# Quad_FC_V10_6.net
KiCad netlist of a schematic drawn in Altium Designer
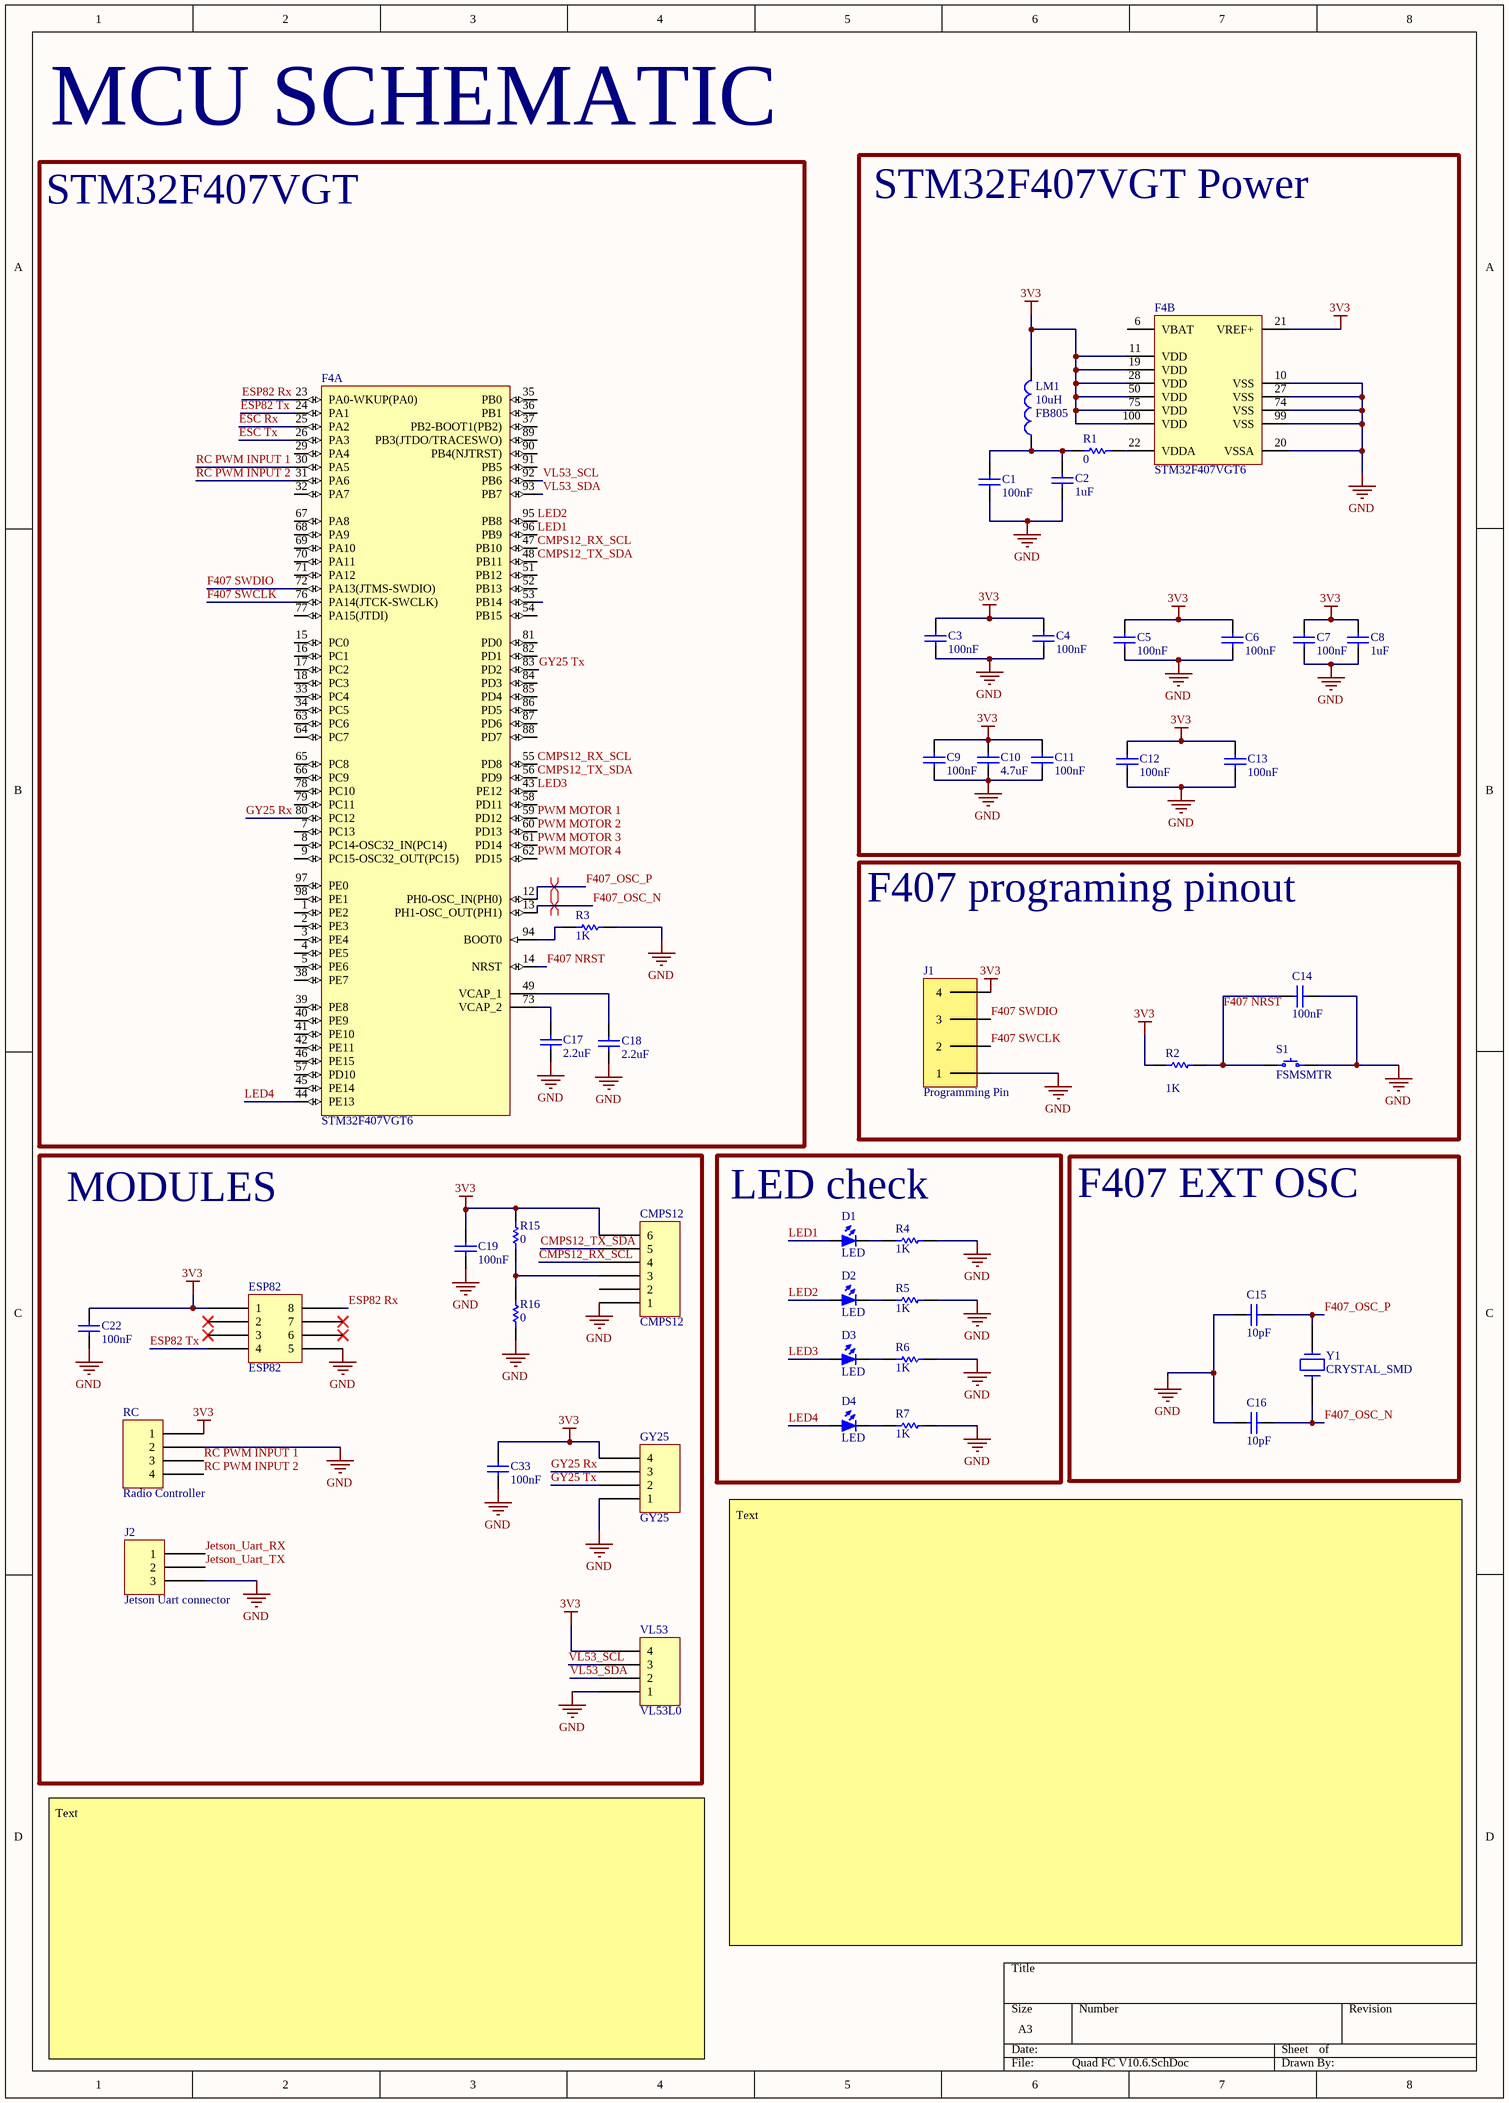
[diagram p0: Quad FC V10.6.SchDoc]

(export (version "E")
  (design (tool "Eeschema 10.0.6"))
  (components
    (comp (ref "C1")
      (value "100nF")
      (footprint "CAP0603")
      (description "F407VET6 Power CAP")
      (fields (field (name "DESIGNER") "Abbas Basereh"))
      (libsource (lib "2017AbbasBasereh9365731239 -ver1") (part "CAP SMD PACKAGE"))
    )
    (comp (ref "C2")
      (value "1uF")
      (footprint "CAP0603")
      (description "F407VET6 Power CAP")
      (fields (field (name "DESIGNER") "Abbas Basereh"))
      (libsource (lib "2017AbbasBasereh9365731239 -ver1") (part "CAP SMD PACKAGE"))
    )
    (comp (ref "C3")
      (value "100nF")
      (footprint "CAP0603")
      (description "F407VET6 Power CAP")
      (fields (field (name "DESIGNER") "Abbas Basereh"))
      (libsource (lib "2017AbbasBasereh9365731239 -ver1") (part "CAP SMD PACKAGE"))
    )
    (comp (ref "C4")
      (value "100nF")
      (footprint "CAP0603")
      (description "F407VET6 Power CAP")
      (fields (field (name "DESIGNER") "Abbas Basereh"))
      (libsource (lib "2017AbbasBasereh9365731239 -ver1") (part "CAP SMD PACKAGE"))
    )
    (comp (ref "C5")
      (value "100nF")
      (footprint "CAP0603")
      (description "F407VET6 Power CAP")
      (fields (field (name "DESIGNER") "Abbas Basereh"))
      (libsource (lib "2017AbbasBasereh9365731239 -ver1") (part "CAP SMD PACKAGE"))
    )
    (comp (ref "C6")
      (value "100nF")
      (footprint "CAP0603")
      (description "F407VET6 Power CAP")
      (fields (field (name "DESIGNER") "Abbas Basereh"))
      (libsource (lib "2017AbbasBasereh9365731239 -ver1") (part "CAP SMD PACKAGE"))
    )
    (comp (ref "C7")
      (value "100nF")
      (footprint "CAP0603")
      (description "F407VET6 Power CAP")
      (fields (field (name "DESIGNER") "Abbas Basereh"))
      (libsource (lib "2017AbbasBasereh9365731239 -ver1") (part "CAP SMD PACKAGE"))
    )
    (comp (ref "C8")
      (value "1uF")
      (footprint "CAP0603")
      (description "F407VET6 Power CAP")
      (fields (field (name "DESIGNER") "Abbas Basereh"))
      (libsource (lib "2017AbbasBasereh9365731239 -ver1") (part "CAP SMD PACKAGE"))
    )
    (comp (ref "C9")
      (value "100nF")
      (footprint "CAP0603")
      (description "F407VET6 Power CAP")
      (fields (field (name "DESIGNER") "Abbas Basereh"))
      (libsource (lib "2017AbbasBasereh9365731239 -ver1") (part "CAP SMD PACKAGE"))
    )
    (comp (ref "C10")
      (value "4.7uF")
      (footprint "CAP0603")
      (description "F407VET6 Power CAP")
      (fields (field (name "DESIGNER") "Abbas Basereh"))
      (libsource (lib "2017AbbasBasereh9365731239 -ver1") (part "CAP SMD PACKAGE"))
    )
    (comp (ref "C11")
      (value "100nF")
      (footprint "CAP0603")
      (description "F407VET6 Power CAP")
      (fields (field (name "DESIGNER") "Abbas Basereh"))
      (libsource (lib "2017AbbasBasereh9365731239 -ver1") (part "CAP SMD PACKAGE"))
    )
    (comp (ref "C12")
      (value "100nF")
      (footprint "CAP0603")
      (description "F407VET6 Power CAP")
      (fields (field (name "DESIGNER") "Abbas Basereh"))
      (libsource (lib "2017AbbasBasereh9365731239 -ver1") (part "CAP SMD PACKAGE"))
    )
    (comp (ref "C13")
      (value "100nF")
      (footprint "CAP0603")
      (description "F407VET6 Power CAP")
      (fields (field (name "DESIGNER") "Abbas Basereh"))
      (libsource (lib "2017AbbasBasereh9365731239 -ver1") (part "CAP SMD PACKAGE"))
    )
    (comp (ref "C14")
      (value "100nF")
      (footprint "CAP0603")
      (description "F407VET6 Power CAP")
      (fields (field (name "DESIGNER") "Abbas Basereh"))
      (libsource (lib "2017AbbasBasereh9365731239 -ver1") (part "CAP SMD PACKAGE"))
    )
    (comp (ref "C15")
      (value "10pF")
      (footprint "CAP0603")
      (description "F407VET6 Power CAP")
      (fields (field (name "DESIGNER") "Abbas Basereh"))
      (libsource (lib "2017AbbasBasereh9365731239 -ver1") (part "CAP SMD PACKAGE"))
    )
    (comp (ref "C16")
      (value "10pF")
      (footprint "CAP0603")
      (description "F407VET6 Power CAP")
      (fields (field (name "DESIGNER") "Abbas Basereh"))
      (libsource (lib "2017AbbasBasereh9365731239 -ver1") (part "CAP SMD PACKAGE"))
    )
    (comp (ref "C17")
      (value "2.2uF")
      (footprint "CAP0603")
      (description "F407VET6 Power CAP")
      (fields (field (name "DESIGNER") "Abbas Basereh"))
      (libsource (lib "2017AbbasBasereh9365731239 -ver1") (part "CAP SMD PACKAGE"))
    )
    (comp (ref "C18")
      (value "2.2uF")
      (footprint "CAP0603")
      (description "F407VET6 Power CAP")
      (fields (field (name "DESIGNER") "Abbas Basereh"))
      (libsource (lib "2017AbbasBasereh9365731239 -ver1") (part "CAP SMD PACKAGE"))
    )
    (comp (ref "C19")
      (value "100nF")
      (footprint "CAP0603")
      (description "F407VET6 Power CAP")
      (fields (field (name "DESIGNER") "Abbas Basereh"))
      (libsource (lib "2017AbbasBasereh9365731239 -ver1") (part "CAP SMD PACKAGE"))
    )
    (comp (ref "C22")
      (value "100nF")
      (footprint "CAP0603")
      (description "F407VET6 Power CAP")
      (fields (field (name "DESIGNER") "Abbas Basereh"))
      (libsource (lib "2017AbbasBasereh9365731239 -ver1") (part "CAP SMD PACKAGE"))
    )
    (comp (ref "C33")
      (value "100nF")
      (footprint "CAP0603")
      (description "F407VET6 Power CAP")
      (fields (field (name "DESIGNER") "Abbas Basereh"))
      (libsource (lib "2017AbbasBasereh9365731239 -ver1") (part "CAP SMD PACKAGE"))
    )
    (comp (ref "CMPS12")
      (value "CMPS12")
      (footprint "SAMTEC SSW-106-03-T-S")
      (description "CONN RCPT 6POS 0.1 TIN PCB")
      (fields (field (name "PART NUMBER") "SSW-106-03-T-S") (field (name "MANUFACTURER") "Samtec Inc."))
      (libsource (lib "Celestial Altium Library - altium_library (1)") (part "6 Pin"))
    )
    (comp (ref "D1")
      (value "LED")
      (footprint "0603 - LED")
      (description "Led")
      (fields (field (name "PUBLISHER") "Altium Limited"))
      (libsource (lib "Sajad_Altium_Library") (part "LED"))
    )
    (comp (ref "D2")
      (value "LED")
      (footprint "0603 - LED")
      (description "Led")
      (fields (field (name "PUBLISHER") "Altium Limited"))
      (libsource (lib "Sajad_Altium_Library") (part "LED"))
    )
    (comp (ref "D3")
      (value "LED")
      (footprint "0603 - LED")
      (description "Led")
      (fields (field (name "PUBLISHER") "Altium Limited"))
      (libsource (lib "Sajad_Altium_Library") (part "LED"))
    )
    (comp (ref "D4")
      (value "LED")
      (footprint "0603 - LED")
      (description "Led")
      (fields (field (name "PUBLISHER") "Altium Limited"))
      (libsource (lib "Sajad_Altium_Library") (part "LED"))
    )
    (comp (ref "ESP82")
      (value "ESP82")
      (footprint "HARWIN M20-7830445")
      (description "CONN RCPT 8POS 0.1 GOLD PCB")
      (fields (field (name "PART NUMBER") "M20-7830442") (field (name "MANUFACTURER") "Harwin Inc."))
      (libsource (lib "Celestial Altium Library - altium_library (1)") (part "2X4 PIN DU"))
    )
    (comp (ref "F4")
      (value "STM32F407VGT6")
      (footprint "STM-LQFP100_N")
      (fields (field (name "MANUFACTURER") "STMicroelectronics"))
      (libsource (lib "STMicroelectronics STM32 F4") (part "STM32F407VGT6"))
    )
    (comp (ref "GY25")
      (value "GY25")
      (footprint "SAMTEC SSW-104-03-T-S")
      (description "CONN RCPT 4POS 0.1 TIN PCB")
      (fields (field (name "PART NUMBER") "SSW-104-03-T-S") (field (name "MANUFACTURER") "Samtec Inc."))
      (libsource (lib "Celestial Altium Library - altium_library (1)") (part "4 Pin"))
    )
    (comp (ref "J1")
      (value "Programming Pin")
      (footprint "HEADER 4X1")
      (libsource (lib "AltiumLib1") (part "Header4X1"))
    )
    (comp (ref "J2")
      (value "Jetson Uart connector")
      (footprint "JST XH B3B-XH-A")
      (description "CONN HEADER VERT 3POS 2.5MM")
      (fields
        (field (name "PART NUMBER") "B3B-XH-A(LF)(SN)")
        (field (name "MANUFACTURER") "JST Sales America Inc.")
      )
      (libsource (lib "Celestial Altium Library - altium_library (1)") (part "3 Pin"))
    )
    (comp (ref "LM1")
      (value "10uH")
      (footprint "0805L")
      (description "Inductor")
      (fields (field (name "ALTIUM_VALUE") "FB805") (field (name "PUBLISHER") "Altium Limited"))
      (libsource (lib "2017AbbasBasereh9365731239 -ver1") (part "L SMA 0.25W"))
    )
    (comp (ref "R1")
      (value "0")
      (footprint "RES0603")
      (description "TOTAL SMD RESISTOR PACK")
      (fields (field (name "DESIGNER") "Abbas Basereh"))
      (libsource (lib "2017AbbasBasereh9365731239 -ver1") (part "RES SMD PACKAGE"))
    )
    (comp (ref "R2")
      (value "1K")
      (footprint "RES0603")
      (description "TOTAL SMD RESISTOR PACK")
      (fields (field (name "DESIGNER") "Abbas Basereh"))
      (libsource (lib "2017AbbasBasereh9365731239 -ver1") (part "RES SMD PACKAGE"))
    )
    (comp (ref "R3")
      (value "1K")
      (footprint "RES0603")
      (description "TOTAL SMD RESISTOR PACK")
      (fields (field (name "DESIGNER") "Abbas Basereh"))
      (libsource (lib "2017AbbasBasereh9365731239 -ver1") (part "RES SMD PACKAGE"))
    )
    (comp (ref "R4")
      (value "1K")
      (footprint "RES0603")
      (description "TOTAL SMD RESISTOR PACK")
      (fields (field (name "DESIGNER") "Abbas Basereh"))
      (libsource (lib "2017AbbasBasereh9365731239 -ver1") (part "RES SMD PACKAGE"))
    )
    (comp (ref "R5")
      (value "1K")
      (footprint "RES0603")
      (description "TOTAL SMD RESISTOR PACK")
      (fields (field (name "DESIGNER") "Abbas Basereh"))
      (libsource (lib "2017AbbasBasereh9365731239 -ver1") (part "RES SMD PACKAGE"))
    )
    (comp (ref "R6")
      (value "1K")
      (footprint "RES0603")
      (description "TOTAL SMD RESISTOR PACK")
      (fields (field (name "DESIGNER") "Abbas Basereh"))
      (libsource (lib "2017AbbasBasereh9365731239 -ver1") (part "RES SMD PACKAGE"))
    )
    (comp (ref "R7")
      (value "1K")
      (footprint "RES0603")
      (description "TOTAL SMD RESISTOR PACK")
      (fields (field (name "DESIGNER") "Abbas Basereh"))
      (libsource (lib "2017AbbasBasereh9365731239 -ver1") (part "RES SMD PACKAGE"))
    )
    (comp (ref "R15")
      (value "0")
      (footprint "RES0603")
      (description "TOTAL SMD RESISTOR PACK")
      (fields (field (name "DESIGNER") "Abbas Basereh"))
      (libsource (lib "2017AbbasBasereh9365731239 -ver1") (part "RES SMD PACKAGE"))
    )
    (comp (ref "R16")
      (value "0")
      (footprint "RES0603")
      (description "TOTAL SMD RESISTOR PACK")
      (fields (field (name "DESIGNER") "Abbas Basereh"))
      (libsource (lib "2017AbbasBasereh9365731239 -ver1") (part "RES SMD PACKAGE"))
    )
    (comp (ref "RC")
      (value "Radio Controller")
      (footprint "JST SM04B-GHS-TB")
      (description "CONN HEADER SMD R/A 4POS 1.25MM")
      (fields
        (field (name "PART NUMBER") "SM04B-GHS-TB(LF)(SN)-")
        (field (name "MANUFACTURER") "JST Sales America Inc.")
      )
      (libsource (lib "") (part "4 Pin_1"))
    )
    (comp (ref "S1")
      (value "FSMSMTR")
      (footprint "TE FSMSMTR")
      (description "SWITCH TACTILE SPST-NO 0.05A 24V")
      (fields (field (name "MANUFACTURER") "TE Connectivity ALCOSWITCH Switches"))
      (libsource (lib "Celestial Altium Library - altium_library (1)") (part "SPST-NO 2 PIN"))
    )
    (comp (ref "VL53")
      (value "VL53L0")
      (footprint "JST SM04B-GHS-TB")
      (description "CONN HEADER SMD R/A 4POS 1.25MM")
      (fields
        (field (name "PART NUMBER") "SM04B-GHS-TB(LF)(SN)-")
        (field (name "MANUFACTURER") "JST Sales America Inc.")
      )
      (libsource (lib "Celestial Altium Library - altium_library (1)") (part "4 Pin"))
    )
    (comp (ref "Y1")
      (value "CRYSTAL_SMD")
      (footprint "My_Crystal - SMD")
      (description "Crystal")
      (libsource (lib "AMINLIB") (part "CRYSTAL_SMD"))
    )
  )
  (nets
    (net (code "1") (name "/CMPS12_RX_SCL") (class "Default")
      (node (ref "CMPS12") (pin "4") (pinfunction "4_4") (pintype "passive"))
      (node (ref "F4") (pin "47") (pinfunction "PB10_47") (pintype "bidirectional"))
      (node (ref "F4") (pin "55") (pinfunction "PD8_55") (pintype "bidirectional"))
    )
    (net (code "2") (name "/CMPS12_TX_SDA") (class "Default")
      (node (ref "CMPS12") (pin "5") (pinfunction "5_5") (pintype "passive"))
      (node (ref "F4") (pin "48") (pinfunction "PB11_48") (pintype "bidirectional"))
      (node (ref "F4") (pin "56") (pinfunction "PD9_56") (pintype "bidirectional"))
    )
    (net (code "3") (name "/ESC Rx") (class "Default")
      (node (ref "F4") (pin "25") (pinfunction "PA2_25") (pintype "bidirectional"))
    )
    (net (code "4") (name "/ESC Tx") (class "Default")
      (node (ref "F4") (pin "26") (pinfunction "PA3_26") (pintype "bidirectional"))
    )
    (net (code "5") (name "/ESP82 Rx") (class "Default")
      (node (ref "ESP82") (pin "8") (pinfunction "8_8") (pintype "passive"))
      (node (ref "F4") (pin "23") (pinfunction "PA0-WKUP(PA0)_23") (pintype "bidirectional"))
    )
    (net (code "6") (name "/ESP82 Tx") (class "Default")
      (node (ref "ESP82") (pin "4") (pinfunction "4_4") (pintype "passive"))
      (node (ref "F4") (pin "24") (pinfunction "PA1_24") (pintype "bidirectional"))
    )
    (net (code "7") (name "/F407 NRST") (class "Default")
      (node (ref "C14") (pin "1") (pinfunction "1_1") (pintype "passive"))
      (node (ref "F4") (pin "14") (pinfunction "NRST_14") (pintype "bidirectional"))
      (node (ref "R2") (pin "2") (pinfunction "2_2") (pintype "passive"))
      (node (ref "S1") (pin "1") (pinfunction "1_1") (pintype "passive"))
    )
    (net (code "8") (name "/F407 SWCLK") (class "Default")
      (node (ref "F4") (pin "76") (pinfunction "PA14(JTCK-SWCLK)_76") (pintype "bidirectional"))
      (node (ref "J1") (pin "2") (pinfunction "2_2") (pintype "passive"))
    )
    (net (code "9") (name "/F407 SWDIO") (class "Default")
      (node (ref "F4") (pin "72") (pinfunction "PA13(JTMS-SWDIO)_72") (pintype "bidirectional"))
      (node (ref "J1") (pin "3") (pinfunction "3_3") (pintype "passive"))
    )
    (net (code "10") (name "/F407_OSC_N") (class "Default")
      (node (ref "C16") (pin "1") (pinfunction "1_1") (pintype "passive"))
      (node (ref "F4") (pin "13") (pinfunction "PH1-OSC_OUT(PH1)_13") (pintype "bidirectional"))
      (node (ref "Y1") (pin "1") (pinfunction "1_1") (pintype "passive"))
    )
    (net (code "11") (name "/F407_OSC_P") (class "Default")
      (node (ref "C15") (pin "2") (pinfunction "2_2") (pintype "passive"))
      (node (ref "F4") (pin "12") (pinfunction "PH0-OSC_IN(PH0)_12") (pintype "bidirectional"))
      (node (ref "Y1") (pin "2") (pinfunction "2_2") (pintype "passive"))
    )
    (net (code "12") (name "/GY25 Rx") (class "Default")
      (node (ref "F4") (pin "80") (pinfunction "PC12_80") (pintype "bidirectional"))
      (node (ref "GY25") (pin "3") (pinfunction "3_3") (pintype "passive"))
    )
    (net (code "13") (name "/GY25 Tx") (class "Default")
      (node (ref "F4") (pin "83") (pinfunction "PD2_83") (pintype "bidirectional"))
      (node (ref "GY25") (pin "2") (pinfunction "2_2") (pintype "passive"))
    )
    (net (code "14") (name "/Jetson_Uart_RX") (class "Default")
      (node (ref "J2") (pin "1") (pinfunction "1_1") (pintype "passive"))
    )
    (net (code "15") (name "/Jetson_Uart_TX") (class "Default")
      (node (ref "J2") (pin "2") (pinfunction "2_2") (pintype "passive"))
    )
    (net (code "16") (name "/LED1") (class "Default")
      (node (ref "D1") (pin "1") (pinfunction "A_1") (pintype "passive"))
      (node (ref "F4") (pin "96") (pinfunction "PB9_96") (pintype "bidirectional"))
    )
    (net (code "17") (name "/LED2") (class "Default")
      (node (ref "D2") (pin "1") (pinfunction "A_1") (pintype "passive"))
      (node (ref "F4") (pin "95") (pinfunction "PB8_95") (pintype "bidirectional"))
    )
    (net (code "18") (name "/LED3") (class "Default")
      (node (ref "D3") (pin "1") (pinfunction "A_1") (pintype "passive"))
      (node (ref "F4") (pin "43") (pinfunction "PE12_43") (pintype "bidirectional"))
    )
    (net (code "19") (name "/LED4") (class "Default")
      (node (ref "D4") (pin "1") (pinfunction "A_1") (pintype "passive"))
      (node (ref "F4") (pin "44") (pinfunction "PE13_44") (pintype "bidirectional"))
    )
    (net (code "20") (name "/PWM MOTOR 1") (class "Default")
      (node (ref "F4") (pin "59") (pinfunction "PD12_59") (pintype "bidirectional"))
    )
    (net (code "21") (name "/PWM MOTOR 2") (class "Default")
      (node (ref "F4") (pin "60") (pinfunction "PD13_60") (pintype "bidirectional"))
    )
    (net (code "22") (name "/PWM MOTOR 3") (class "Default")
      (node (ref "F4") (pin "61") (pinfunction "PD14_61") (pintype "bidirectional"))
    )
    (net (code "23") (name "/PWM MOTOR 4") (class "Default")
      (node (ref "F4") (pin "62") (pinfunction "PD15_62") (pintype "bidirectional"))
    )
    (net (code "24") (name "/RC PWM INPUT 1") (class "Default")
      (node (ref "F4") (pin "30") (pinfunction "PA5_30") (pintype "bidirectional"))
      (node (ref "RC") (pin "3") (pinfunction "3_3") (pintype "passive"))
    )
    (net (code "25") (name "/RC PWM INPUT 2") (class "Default")
      (node (ref "F4") (pin "31") (pinfunction "PA6_31") (pintype "bidirectional"))
      (node (ref "RC") (pin "4") (pinfunction "4_4") (pintype "passive"))
    )
    (net (code "26") (name "/VL53_SCL") (class "Default")
      (node (ref "F4") (pin "92") (pinfunction "PB6_92") (pintype "bidirectional"))
      (node (ref "VL53") (pin "3") (pinfunction "3_3") (pintype "passive"))
    )
    (net (code "27") (name "/VL53_SDA") (class "Default")
      (node (ref "F4") (pin "93") (pinfunction "PB7_93") (pintype "bidirectional"))
      (node (ref "VL53") (pin "2") (pinfunction "2_2") (pintype "passive"))
    )
    (net (code "28") (name "3V3") (class "Default")
      (node (ref "C10") (pin "2") (pinfunction "2_2") (pintype "passive"))
      (node (ref "C11") (pin "2") (pinfunction "2_2") (pintype "passive"))
      (node (ref "C12") (pin "2") (pinfunction "2_2") (pintype "passive"))
      (node (ref "C13") (pin "2") (pinfunction "2_2") (pintype "passive"))
      (node (ref "C19") (pin "1") (pinfunction "1_1") (pintype "passive"))
      (node (ref "C22") (pin "1") (pinfunction "1_1") (pintype "passive"))
      (node (ref "C3") (pin "2") (pinfunction "2_2") (pintype "passive"))
      (node (ref "C33") (pin "1") (pinfunction "1_1") (pintype "passive"))
      (node (ref "C4") (pin "2") (pinfunction "2_2") (pintype "passive"))
      (node (ref "C5") (pin "2") (pinfunction "2_2") (pintype "passive"))
      (node (ref "C6") (pin "2") (pinfunction "2_2") (pintype "passive"))
      (node (ref "C7") (pin "1") (pinfunction "1_1") (pintype "passive"))
      (node (ref "C8") (pin "1") (pinfunction "1_1") (pintype "passive"))
      (node (ref "C9") (pin "2") (pinfunction "2_2") (pintype "passive"))
      (node (ref "CMPS12") (pin "6") (pinfunction "6_6") (pintype "passive"))
      (node (ref "ESP82") (pin "1") (pinfunction "1_1") (pintype "passive"))
      (node (ref "F4") (pin "100") (pinfunction "VDD_100") (pintype "power_in"))
      (node (ref "F4") (pin "11") (pinfunction "VDD_11") (pintype "power_in"))
      (node (ref "F4") (pin "19") (pinfunction "VDD_19") (pintype "power_in"))
      (node (ref "F4") (pin "21") (pinfunction "VREF+_21") (pintype "power_in"))
      (node (ref "F4") (pin "28") (pinfunction "VDD_28") (pintype "power_in"))
      (node (ref "F4") (pin "50") (pinfunction "VDD_50") (pintype "power_in"))
      (node (ref "F4") (pin "75") (pinfunction "VDD_75") (pintype "power_in"))
      (node (ref "GY25") (pin "4") (pinfunction "4_4") (pintype "passive"))
      (node (ref "J1") (pin "4") (pinfunction "4_4") (pintype "passive"))
      (node (ref "LM1") (pin "2") (pinfunction "2_2") (pintype "passive"))
      (node (ref "R15") (pin "2") (pinfunction "2_2") (pintype "passive"))
      (node (ref "R2") (pin "1") (pinfunction "1_1") (pintype "passive"))
      (node (ref "RC") (pin "1") (pinfunction "1_1") (pintype "passive"))
      (node (ref "VL53") (pin "4") (pinfunction "4_4") (pintype "passive"))
    )
    (net (code "29") (name "GND") (class "Default")
      (node (ref "C1") (pin "1") (pinfunction "1_1") (pintype "passive"))
      (node (ref "C10") (pin "1") (pinfunction "1_1") (pintype "passive"))
      (node (ref "C11") (pin "1") (pinfunction "1_1") (pintype "passive"))
      (node (ref "C12") (pin "1") (pinfunction "1_1") (pintype "passive"))
      (node (ref "C13") (pin "1") (pinfunction "1_1") (pintype "passive"))
      (node (ref "C14") (pin "2") (pinfunction "2_2") (pintype "passive"))
      (node (ref "C15") (pin "1") (pinfunction "1_1") (pintype "passive"))
      (node (ref "C16") (pin "2") (pinfunction "2_2") (pintype "passive"))
      (node (ref "C17") (pin "2") (pinfunction "2_2") (pintype "passive"))
      (node (ref "C18") (pin "2") (pinfunction "2_2") (pintype "passive"))
      (node (ref "C19") (pin "2") (pinfunction "2_2") (pintype "passive"))
      (node (ref "C2") (pin "1") (pinfunction "1_1") (pintype "passive"))
      (node (ref "C22") (pin "2") (pinfunction "2_2") (pintype "passive"))
      (node (ref "C3") (pin "1") (pinfunction "1_1") (pintype "passive"))
      (node (ref "C33") (pin "2") (pinfunction "2_2") (pintype "passive"))
      (node (ref "C4") (pin "1") (pinfunction "1_1") (pintype "passive"))
      (node (ref "C5") (pin "1") (pinfunction "1_1") (pintype "passive"))
      (node (ref "C6") (pin "1") (pinfunction "1_1") (pintype "passive"))
      (node (ref "C7") (pin "2") (pinfunction "2_2") (pintype "passive"))
      (node (ref "C8") (pin "2") (pinfunction "2_2") (pintype "passive"))
      (node (ref "C9") (pin "1") (pinfunction "1_1") (pintype "passive"))
      (node (ref "CMPS12") (pin "1") (pinfunction "1_1") (pintype "passive"))
      (node (ref "ESP82") (pin "5") (pinfunction "5_5") (pintype "passive"))
      (node (ref "F4") (pin "10") (pinfunction "VSS_10") (pintype "power_in"))
      (node (ref "F4") (pin "20") (pinfunction "VSSA_20") (pintype "power_in"))
      (node (ref "F4") (pin "27") (pinfunction "VSS_27") (pintype "power_in"))
      (node (ref "F4") (pin "74") (pinfunction "VSS_74") (pintype "power_in"))
      (node (ref "F4") (pin "99") (pinfunction "VSS_99") (pintype "power_in"))
      (node (ref "GY25") (pin "1") (pinfunction "1_1") (pintype "passive"))
      (node (ref "J1") (pin "1") (pinfunction "1_1") (pintype "passive"))
      (node (ref "J2") (pin "3") (pinfunction "3_3") (pintype "passive"))
      (node (ref "R16") (pin "1") (pinfunction "1_1") (pintype "passive"))
      (node (ref "R3") (pin "2") (pinfunction "2_2") (pintype "passive"))
      (node (ref "R4") (pin "2") (pinfunction "2_2") (pintype "passive"))
      (node (ref "R5") (pin "2") (pinfunction "2_2") (pintype "passive"))
      (node (ref "R6") (pin "2") (pinfunction "2_2") (pintype "passive"))
      (node (ref "R7") (pin "2") (pinfunction "2_2") (pintype "passive"))
      (node (ref "RC") (pin "2") (pinfunction "2_2") (pintype "passive"))
      (node (ref "S1") (pin "2") (pinfunction "2_2") (pintype "passive"))
      (node (ref "VL53") (pin "1") (pinfunction "1_1") (pintype "passive"))
    )
    (net (code "30") (name "Net-(C1-Pad2)") (class "Default")
      (node (ref "C1") (pin "2") (pinfunction "2_2") (pintype "passive"))
      (node (ref "C2") (pin "2") (pinfunction "2_2") (pintype "passive"))
      (node (ref "LM1") (pin "1") (pinfunction "1_1") (pintype "passive"))
      (node (ref "R1") (pin "1") (pinfunction "1_1") (pintype "passive"))
    )
    (net (code "31") (name "Net-(CMPS12-Pad3)") (class "Default")
      (node (ref "CMPS12") (pin "3") (pinfunction "3_3") (pintype "passive"))
      (node (ref "R15") (pin "1") (pinfunction "1_1") (pintype "passive"))
      (node (ref "R16") (pin "2") (pinfunction "2_2") (pintype "passive"))
    )
    (net (code "32") (name "Net-(D1-K)") (class "Default")
      (node (ref "D1") (pin "2") (pinfunction "K_2") (pintype "passive"))
      (node (ref "R4") (pin "1") (pinfunction "1_1") (pintype "passive"))
    )
    (net (code "33") (name "Net-(D2-K)") (class "Default")
      (node (ref "D2") (pin "2") (pinfunction "K_2") (pintype "passive"))
      (node (ref "R5") (pin "1") (pinfunction "1_1") (pintype "passive"))
    )
    (net (code "34") (name "Net-(D3-K)") (class "Default")
      (node (ref "D3") (pin "2") (pinfunction "K_2") (pintype "passive"))
      (node (ref "R6") (pin "1") (pinfunction "1_1") (pintype "passive"))
    )
    (net (code "35") (name "Net-(D4-K)") (class "Default")
      (node (ref "D4") (pin "2") (pinfunction "K_2") (pintype "passive"))
      (node (ref "R7") (pin "1") (pinfunction "1_1") (pintype "passive"))
    )
    (net (code "36") (name "Net-(F4A-BOOT0)") (class "Default")
      (node (ref "F4") (pin "94") (pinfunction "BOOT0_94") (pintype "input"))
      (node (ref "R3") (pin "1") (pinfunction "1_1") (pintype "passive"))
    )
    (net (code "37") (name "Net-(F4A-VCAP_1)") (class "Default")
      (node (ref "C18") (pin "1") (pinfunction "1_1") (pintype "passive"))
      (node (ref "F4") (pin "49") (pinfunction "VCAP_1_49") (pintype "power_in"))
    )
    (net (code "38") (name "Net-(F4A-VCAP_2)") (class "Default")
      (node (ref "C17") (pin "1") (pinfunction "1_1") (pintype "passive"))
      (node (ref "F4") (pin "73") (pinfunction "VCAP_2_73") (pintype "power_in"))
    )
    (net (code "39") (name "Net-(F4B-VDDA)") (class "Default")
      (node (ref "F4") (pin "22") (pinfunction "VDDA_22") (pintype "power_in"))
      (node (ref "R1") (pin "2") (pinfunction "2_2") (pintype "passive"))
    )
    (net (code "40") (name "unconnected-(CMPS12-Pad2)") (class "Default")
      (node (ref "CMPS12") (pin "2") (pinfunction "2_2") (pintype "passive"))
    )
    (net (code "41") (name "unconnected-(ESP82-Pad2)") (class "Default")
      (node (ref "ESP82") (pin "2") (pinfunction "2_2") (pintype "passive+no_connect"))
    )
    (net (code "42") (name "unconnected-(ESP82-Pad3)") (class "Default")
      (node (ref "ESP82") (pin "3") (pinfunction "3_3") (pintype "passive+no_connect"))
    )
    (net (code "43") (name "unconnected-(ESP82-Pad6)") (class "Default")
      (node (ref "ESP82") (pin "6") (pinfunction "6_6") (pintype "passive+no_connect"))
    )
    (net (code "44") (name "unconnected-(ESP82-Pad7)") (class "Default")
      (node (ref "ESP82") (pin "7") (pinfunction "7_7") (pintype "passive+no_connect"))
    )
    (net (code "45") (name "unconnected-(F4A-PA4-Pad29)") (class "Default")
      (node (ref "F4") (pin "29") (pinfunction "PA4_29") (pintype "bidirectional"))
    )
    (net (code "46") (name "unconnected-(F4A-PA7-Pad32)") (class "Default")
      (node (ref "F4") (pin "32") (pinfunction "PA7_32") (pintype "bidirectional"))
    )
    (net (code "47") (name "unconnected-(F4A-PA8-Pad67)") (class "Default")
      (node (ref "F4") (pin "67") (pinfunction "PA8_67") (pintype "bidirectional"))
    )
    (net (code "48") (name "unconnected-(F4A-PA9-Pad68)") (class "Default")
      (node (ref "F4") (pin "68") (pinfunction "PA9_68") (pintype "bidirectional"))
    )
    (net (code "49") (name "unconnected-(F4A-PA10-Pad69)") (class "Default")
      (node (ref "F4") (pin "69") (pinfunction "PA10_69") (pintype "bidirectional"))
    )
    (net (code "50") (name "unconnected-(F4A-PA11-Pad70)") (class "Default")
      (node (ref "F4") (pin "70") (pinfunction "PA11_70") (pintype "bidirectional"))
    )
    (net (code "51") (name "unconnected-(F4A-PA12-Pad71)") (class "Default")
      (node (ref "F4") (pin "71") (pinfunction "PA12_71") (pintype "bidirectional"))
    )
    (net (code "52") (name "unconnected-(F4A-PA15(JTDI)-Pad77)") (class "Default")
      (node (ref "F4") (pin "77") (pinfunction "PA15(JTDI)_77") (pintype "bidirectional"))
    )
    (net (code "53") (name "unconnected-(F4A-PB0-Pad35)") (class "Default")
      (node (ref "F4") (pin "35") (pinfunction "PB0_35") (pintype "bidirectional"))
    )
    (net (code "54") (name "unconnected-(F4A-PB1-Pad36)") (class "Default")
      (node (ref "F4") (pin "36") (pinfunction "PB1_36") (pintype "bidirectional"))
    )
    (net (code "55") (name "unconnected-(F4A-PB2-BOOT1(PB2)-Pad37)") (class "Default")
      (node (ref "F4") (pin "37") (pinfunction "PB2-BOOT1(PB2)_37") (pintype "bidirectional"))
    )
    (net (code "56") (name "unconnected-(F4A-PB3(JTDO{slash}TRACESWO)-Pad89)") (class "Default")
      (node (ref "F4") (pin "89") (pinfunction "PB3(JTDO/TRACESWO)_89") (pintype "bidirectional"))
    )
    (net (code "57") (name "unconnected-(F4A-PB4(NJTRST)-Pad90)") (class "Default")
      (node (ref "F4") (pin "90") (pinfunction "PB4(NJTRST)_90") (pintype "bidirectional"))
    )
    (net (code "58") (name "unconnected-(F4A-PB5-Pad91)") (class "Default")
      (node (ref "F4") (pin "91") (pinfunction "PB5_91") (pintype "bidirectional"))
    )
    (net (code "59") (name "unconnected-(F4A-PB12-Pad51)") (class "Default")
      (node (ref "F4") (pin "51") (pinfunction "PB12_51") (pintype "bidirectional"))
    )
    (net (code "60") (name "unconnected-(F4A-PB13-Pad52)") (class "Default")
      (node (ref "F4") (pin "52") (pinfunction "PB13_52") (pintype "bidirectional"))
    )
    (net (code "61") (name "unconnected-(F4A-PB14-Pad53)") (class "Default")
      (node (ref "F4") (pin "53") (pinfunction "PB14_53") (pintype "bidirectional"))
    )
    (net (code "62") (name "unconnected-(F4A-PB15-Pad54)") (class "Default")
      (node (ref "F4") (pin "54") (pinfunction "PB15_54") (pintype "bidirectional"))
    )
    (net (code "63") (name "unconnected-(F4A-PC0-Pad15)") (class "Default")
      (node (ref "F4") (pin "15") (pinfunction "PC0_15") (pintype "bidirectional"))
    )
    (net (code "64") (name "unconnected-(F4A-PC1-Pad16)") (class "Default")
      (node (ref "F4") (pin "16") (pinfunction "PC1_16") (pintype "bidirectional"))
    )
    (net (code "65") (name "unconnected-(F4A-PC2-Pad17)") (class "Default")
      (node (ref "F4") (pin "17") (pinfunction "PC2_17") (pintype "bidirectional"))
    )
    (net (code "66") (name "unconnected-(F4A-PC3-Pad18)") (class "Default")
      (node (ref "F4") (pin "18") (pinfunction "PC3_18") (pintype "bidirectional"))
    )
    (net (code "67") (name "unconnected-(F4A-PC4-Pad33)") (class "Default")
      (node (ref "F4") (pin "33") (pinfunction "PC4_33") (pintype "bidirectional"))
    )
    (net (code "68") (name "unconnected-(F4A-PC5-Pad34)") (class "Default")
      (node (ref "F4") (pin "34") (pinfunction "PC5_34") (pintype "bidirectional"))
    )
    (net (code "69") (name "unconnected-(F4A-PC6-Pad63)") (class "Default")
      (node (ref "F4") (pin "63") (pinfunction "PC6_63") (pintype "bidirectional"))
    )
    (net (code "70") (name "unconnected-(F4A-PC7-Pad64)") (class "Default")
      (node (ref "F4") (pin "64") (pinfunction "PC7_64") (pintype "bidirectional"))
    )
    (net (code "71") (name "unconnected-(F4A-PC8-Pad65)") (class "Default")
      (node (ref "F4") (pin "65") (pinfunction "PC8_65") (pintype "bidirectional"))
    )
    (net (code "72") (name "unconnected-(F4A-PC9-Pad66)") (class "Default")
      (node (ref "F4") (pin "66") (pinfunction "PC9_66") (pintype "bidirectional"))
    )
    (net (code "73") (name "unconnected-(F4A-PC10-Pad78)") (class "Default")
      (node (ref "F4") (pin "78") (pinfunction "PC10_78") (pintype "bidirectional"))
    )
    (net (code "74") (name "unconnected-(F4A-PC11-Pad79)") (class "Default")
      (node (ref "F4") (pin "79") (pinfunction "PC11_79") (pintype "bidirectional"))
    )
    (net (code "75") (name "unconnected-(F4A-PC13-Pad7)") (class "Default")
      (node (ref "F4") (pin "7") (pinfunction "PC13_7") (pintype "bidirectional"))
    )
    (net (code "76") (name "unconnected-(F4A-PC14-OSC32_IN(PC14)-Pad8)") (class "Default")
      (node (ref "F4") (pin "8") (pinfunction "PC14-OSC32_IN(PC14)_8") (pintype "bidirectional"))
    )
    (net (code "77") (name "unconnected-(F4A-PC15-OSC32_OUT(PC15)-Pad9)") (class "Default")
      (node (ref "F4") (pin "9") (pinfunction "PC15-OSC32_OUT(PC15)_9") (pintype "bidirectional"))
    )
    (net (code "78") (name "unconnected-(F4A-PD0-Pad81)") (class "Default")
      (node (ref "F4") (pin "81") (pinfunction "PD0_81") (pintype "bidirectional"))
    )
    (net (code "79") (name "unconnected-(F4A-PD1-Pad82)") (class "Default")
      (node (ref "F4") (pin "82") (pinfunction "PD1_82") (pintype "bidirectional"))
    )
    (net (code "80") (name "unconnected-(F4A-PD3-Pad84)") (class "Default")
      (node (ref "F4") (pin "84") (pinfunction "PD3_84") (pintype "bidirectional"))
    )
    (net (code "81") (name "unconnected-(F4A-PD4-Pad85)") (class "Default")
      (node (ref "F4") (pin "85") (pinfunction "PD4_85") (pintype "bidirectional"))
    )
    (net (code "82") (name "unconnected-(F4A-PD5-Pad86)") (class "Default")
      (node (ref "F4") (pin "86") (pinfunction "PD5_86") (pintype "bidirectional"))
    )
    (net (code "83") (name "unconnected-(F4A-PD6-Pad87)") (class "Default")
      (node (ref "F4") (pin "87") (pinfunction "PD6_87") (pintype "bidirectional"))
    )
    (net (code "84") (name "unconnected-(F4A-PD7-Pad88)") (class "Default")
      (node (ref "F4") (pin "88") (pinfunction "PD7_88") (pintype "bidirectional"))
    )
    (net (code "85") (name "unconnected-(F4A-PD10-Pad57)") (class "Default")
      (node (ref "F4") (pin "57") (pinfunction "PD10_57") (pintype "bidirectional"))
    )
    (net (code "86") (name "unconnected-(F4A-PD11-Pad58)") (class "Default")
      (node (ref "F4") (pin "58") (pinfunction "PD11_58") (pintype "bidirectional"))
    )
    (net (code "87") (name "unconnected-(F4A-PE0-Pad97)") (class "Default")
      (node (ref "F4") (pin "97") (pinfunction "PE0_97") (pintype "bidirectional"))
    )
    (net (code "88") (name "unconnected-(F4A-PE1-Pad98)") (class "Default")
      (node (ref "F4") (pin "98") (pinfunction "PE1_98") (pintype "bidirectional"))
    )
    (net (code "89") (name "unconnected-(F4A-PE2-Pad1)") (class "Default")
      (node (ref "F4") (pin "1") (pinfunction "PE2_1") (pintype "bidirectional"))
    )
    (net (code "90") (name "unconnected-(F4A-PE3-Pad2)") (class "Default")
      (node (ref "F4") (pin "2") (pinfunction "PE3_2") (pintype "bidirectional"))
    )
    (net (code "91") (name "unconnected-(F4A-PE4-Pad3)") (class "Default")
      (node (ref "F4") (pin "3") (pinfunction "PE4_3") (pintype "bidirectional"))
    )
    (net (code "92") (name "unconnected-(F4A-PE5-Pad4)") (class "Default")
      (node (ref "F4") (pin "4") (pinfunction "PE5_4") (pintype "bidirectional"))
    )
    (net (code "93") (name "unconnected-(F4A-PE6-Pad5)") (class "Default")
      (node (ref "F4") (pin "5") (pinfunction "PE6_5") (pintype "bidirectional"))
    )
    (net (code "94") (name "unconnected-(F4A-PE7-Pad38)") (class "Default")
      (node (ref "F4") (pin "38") (pinfunction "PE7_38") (pintype "bidirectional"))
    )
    (net (code "95") (name "unconnected-(F4A-PE8-Pad39)") (class "Default")
      (node (ref "F4") (pin "39") (pinfunction "PE8_39") (pintype "bidirectional"))
    )
    (net (code "96") (name "unconnected-(F4A-PE9-Pad40)") (class "Default")
      (node (ref "F4") (pin "40") (pinfunction "PE9_40") (pintype "bidirectional"))
    )
    (net (code "97") (name "unconnected-(F4A-PE10-Pad41)") (class "Default")
      (node (ref "F4") (pin "41") (pinfunction "PE10_41") (pintype "bidirectional"))
    )
    (net (code "98") (name "unconnected-(F4A-PE11-Pad42)") (class "Default")
      (node (ref "F4") (pin "42") (pinfunction "PE11_42") (pintype "bidirectional"))
    )
    (net (code "99") (name "unconnected-(F4A-PE14-Pad45)") (class "Default")
      (node (ref "F4") (pin "45") (pinfunction "PE14_45") (pintype "bidirectional"))
    )
    (net (code "100") (name "unconnected-(F4A-PE15-Pad46)") (class "Default")
      (node (ref "F4") (pin "46") (pinfunction "PE15_46") (pintype "bidirectional"))
    )
    (net (code "101") (name "unconnected-(F4B-VBAT-Pad6)") (class "Default")
      (node (ref "F4") (pin "6") (pinfunction "VBAT_6") (pintype "power_in"))
    )
  )
)
